# Naninator.net
KiCad netlist of a schematic drawn in EAGLE
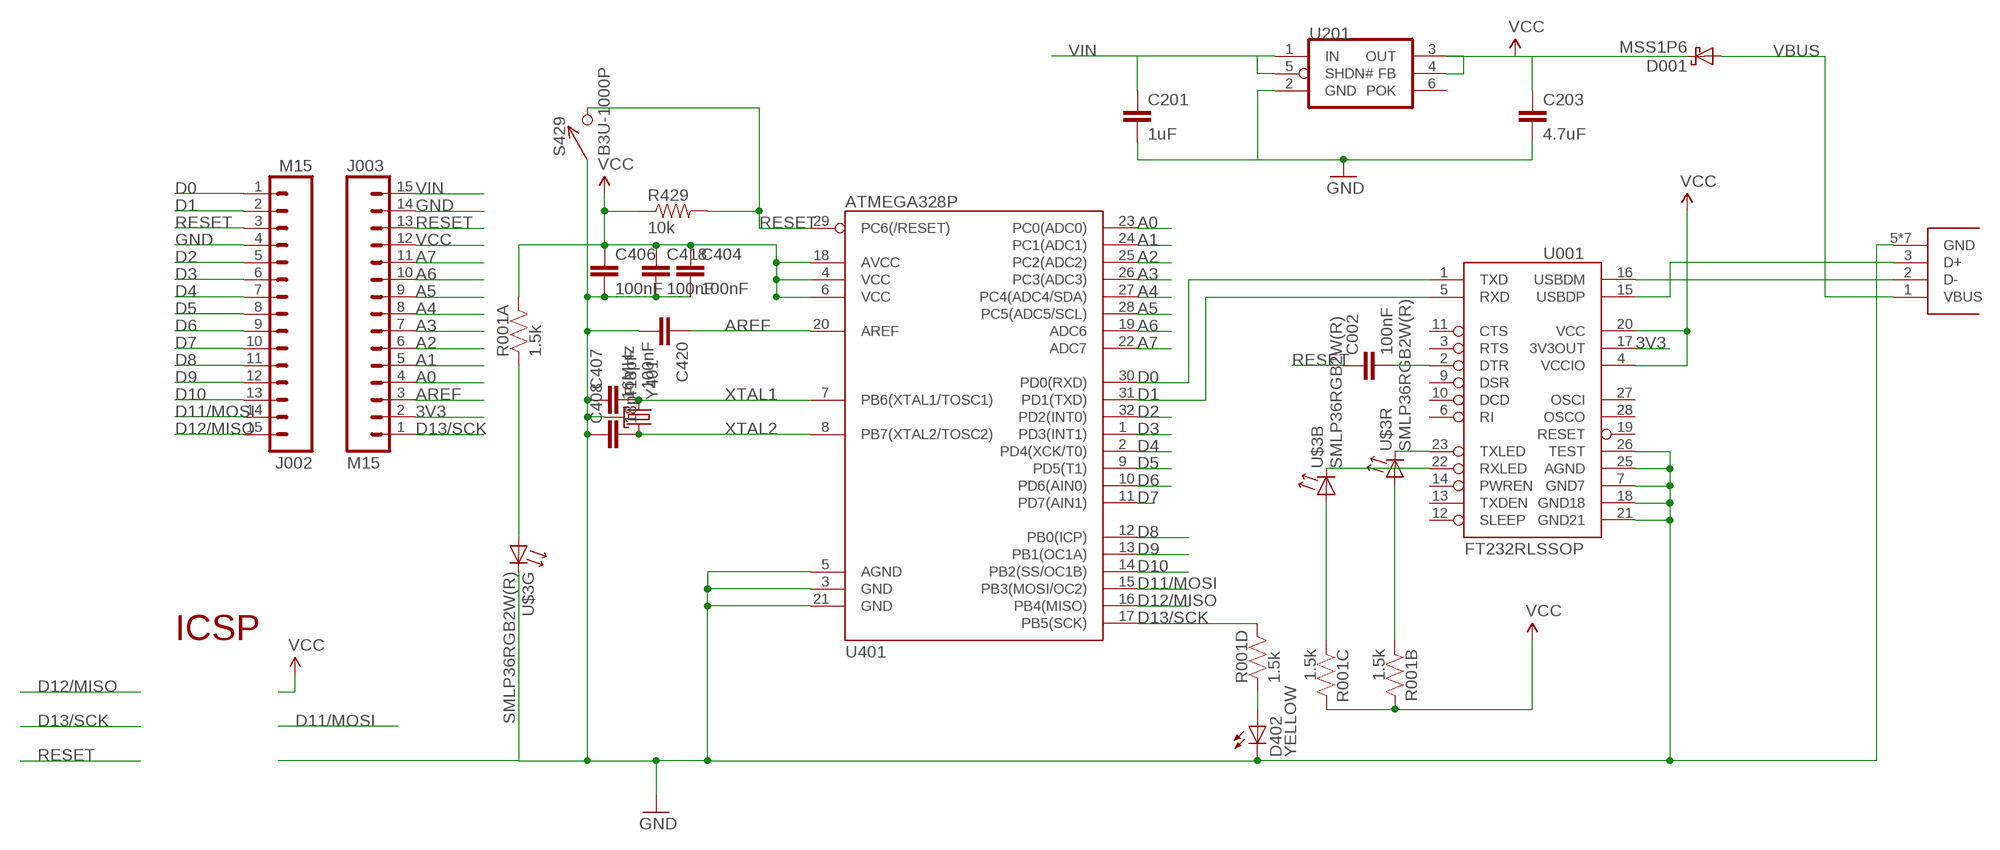
[diagram p0: schematic, sheet 1]

(export (version "E")
  (design (tool "Eeschema 10.0.6"))
  (components
    (comp (ref "C002")
      (value "100nF")
      (footprint "eagle-import:0402-CAP")
      (libsource (lib "eagle-import") (part "CAP0402-CAP"))
    )
    (comp (ref "C201")
      (value "1uF")
      (footprint "eagle-import:0402-CAP")
      (libsource (lib "eagle-import") (part "CAP0402-CAP"))
    )
    (comp (ref "C203")
      (value "4.7uF")
      (footprint "eagle-import:0402-CAP")
      (libsource (lib "eagle-import") (part "CAP0402-CAP"))
    )
    (comp (ref "C404")
      (value "100nF")
      (footprint "eagle-import:0402-CAP")
      (libsource (lib "eagle-import") (part "CAP0402-CAP"))
    )
    (comp (ref "C406")
      (value "100nF")
      (footprint "eagle-import:0402-CAP")
      (libsource (lib "eagle-import") (part "CAP0402-CAP"))
    )
    (comp (ref "C407")
      (value "18pF")
      (footprint "eagle-import:0402-CAP")
      (libsource (lib "eagle-import") (part "CAP0402-CAP"))
    )
    (comp (ref "C408")
      (value "18pF")
      (footprint "eagle-import:0402-CAP")
      (libsource (lib "eagle-import") (part "CAP0402-CAP"))
    )
    (comp (ref "C418")
      (value "100nF")
      (footprint "eagle-import:0402-CAP")
      (libsource (lib "eagle-import") (part "CAP0402-CAP"))
    )
    (comp (ref "C420")
      (value "100nF")
      (footprint "eagle-import:0402-CAP")
      (libsource (lib "eagle-import") (part "CAP0402-CAP"))
    )
    (comp (ref "D001")
      (value "MSS1P6")
      (footprint "eagle-import:MICROSMP")
      (libsource (lib "eagle-import") (part "MSS1P6"))
    )
    (comp (ref "D402")
      (value "YELLOW")
      (footprint "eagle-import:LED-0603")
      (libsource (lib "eagle-import") (part "LED0603"))
    )
    (comp (ref "J001")
      (value "USB_MICROB_JSTGCT")
      (footprint "eagle-import:USB_MICROB_3075")
      (libsource (lib "eagle-import") (part "USB_MICROB_JSTGCT"))
    )
    (comp (ref "J002")
      (value "M15")
      (footprint "eagle-import:1X15")
      (libsource (lib "eagle-import") (part "M15"))
    )
    (comp (ref "J003")
      (value "M15")
      (footprint "eagle-import:1X15")
      (libsource (lib "eagle-import") (part "M15"))
    )
    (comp (ref "R001")
      (value "1.5k")
      (footprint "eagle-import:CRA04")
      (fields (field (name "DIGIKEY") "CRA4S81.5KCT-ND"))
      (libsource (lib "eagle-import") (part "RP404"))
    )
    (comp (ref "R429")
      (value "10k")
      (footprint "eagle-import:0402-RES")
      (libsource (lib "eagle-import") (part "RESISTOR0402-RES"))
    )
    (comp (ref "S429")
      (value "B3U-1000P")
      (footprint "eagle-import:B3U-1000P")
      (libsource (lib "eagle-import") (part "B3U-1000P"))
    )
    (comp (ref "U$3")
      (value "SMLP36RGB2W(R)")
      (footprint "eagle-import:SMLP36")
      (libsource (lib "eagle-import") (part "SMLP36RGB2W(R)"))
    )
    (comp (ref "U001")
      (value "FT232RLSSOP")
      (footprint "eagle-import:SSOP28DB")
      (libsource (lib "eagle-import") (part "FT232RLSSOP"))
    )
    (comp (ref "U201")
      (value "MAX8881")
      (footprint "eagle-import:SOT-23-6")
      (libsource (lib "eagle-import") (part "MAX8881"))
    )
    (comp (ref "U401")
      (value "ATMEGA328P")
      (footprint "eagle-import:TQFP32-08")
      (libsource (lib "eagle-import") (part "ATMEGA168"))
    )
    (comp (ref "Y401")
      (value "16MHz")
      (footprint "eagle-import:CRYSTAL_SMD_2MM_1_6MM")
      (libsource (lib "eagle-import") (part "CX25208Y"))
    )
  )
  (nets
    (net (code "1") (name "/3V3") (class "Default")
      (node (ref "J003") (pin "2") (pinfunction "2_2") (pintype "passive"))
      (node (ref "U001") (pin "17") (pinfunction "3V3OUT_17") (pintype "output"))
    )
    (net (code "2") (name "/A0") (class "Default")
      (node (ref "J003") (pin "4") (pinfunction "4_4") (pintype "passive"))
      (node (ref "U401") (pin "23") (pinfunction "PC0(ADC0)_23") (pintype "bidirectional"))
    )
    (net (code "3") (name "/A1") (class "Default")
      (node (ref "J003") (pin "5") (pinfunction "5_5") (pintype "passive"))
      (node (ref "U401") (pin "24") (pinfunction "PC1(ADC1)_24") (pintype "bidirectional"))
    )
    (net (code "4") (name "/A2") (class "Default")
      (node (ref "J003") (pin "6") (pinfunction "6_6") (pintype "passive"))
      (node (ref "U401") (pin "25") (pinfunction "PC2(ADC2)_25") (pintype "bidirectional"))
    )
    (net (code "5") (name "/A3") (class "Default")
      (node (ref "J003") (pin "7") (pinfunction "7_7") (pintype "passive"))
      (node (ref "U401") (pin "26") (pinfunction "PC3(ADC3)_26") (pintype "bidirectional"))
    )
    (net (code "6") (name "/A4") (class "Default")
      (node (ref "J003") (pin "8") (pinfunction "8_8") (pintype "passive"))
      (node (ref "U401") (pin "27") (pinfunction "PC4(ADC4/SDA)_27") (pintype "bidirectional"))
    )
    (net (code "7") (name "/A5") (class "Default")
      (node (ref "J003") (pin "9") (pinfunction "9_9") (pintype "passive"))
      (node (ref "U401") (pin "28") (pinfunction "PC5(ADC5/SCL)_28") (pintype "bidirectional"))
    )
    (net (code "8") (name "/A6") (class "Default")
      (node (ref "J003") (pin "10") (pinfunction "10_10") (pintype "passive"))
      (node (ref "U401") (pin "19") (pinfunction "ADC6_19") (pintype "bidirectional"))
    )
    (net (code "9") (name "/A7") (class "Default")
      (node (ref "J003") (pin "11") (pinfunction "11_11") (pintype "passive"))
      (node (ref "U401") (pin "22") (pinfunction "ADC7_22") (pintype "bidirectional"))
    )
    (net (code "10") (name "/AREF") (class "Default")
      (node (ref "C420") (pin "1") (pinfunction "1_1") (pintype "passive"))
      (node (ref "J003") (pin "3") (pinfunction "3_3") (pintype "passive"))
      (node (ref "U401") (pin "20") (pinfunction "AREF_20") (pintype "bidirectional"))
    )
    (net (code "11") (name "/D0") (class "Default")
      (node (ref "J002") (pin "1") (pinfunction "1_1") (pintype "passive"))
      (node (ref "U001") (pin "1") (pinfunction "TXD_1") (pintype "output"))
      (node (ref "U401") (pin "30") (pinfunction "PD0(RXD)_30") (pintype "bidirectional"))
    )
    (net (code "12") (name "/D1") (class "Default")
      (node (ref "J002") (pin "2") (pinfunction "2_2") (pintype "passive"))
      (node (ref "U001") (pin "5") (pinfunction "RXD_5") (pintype "input"))
      (node (ref "U401") (pin "31") (pinfunction "PD1(TXD)_31") (pintype "bidirectional"))
    )
    (net (code "13") (name "/D2") (class "Default")
      (node (ref "J002") (pin "5") (pinfunction "5_5") (pintype "passive"))
      (node (ref "U401") (pin "32") (pinfunction "PD2(INT0)_32") (pintype "bidirectional"))
    )
    (net (code "14") (name "/D3") (class "Default")
      (node (ref "J002") (pin "6") (pinfunction "6_6") (pintype "passive"))
      (node (ref "U401") (pin "1") (pinfunction "PD3(INT1)_1") (pintype "bidirectional"))
    )
    (net (code "15") (name "/D4") (class "Default")
      (node (ref "J002") (pin "7") (pinfunction "7_7") (pintype "passive"))
      (node (ref "U401") (pin "2") (pinfunction "PD4(XCK/T0)_2") (pintype "bidirectional"))
    )
    (net (code "16") (name "/D5") (class "Default")
      (node (ref "J002") (pin "8") (pinfunction "8_8") (pintype "passive"))
      (node (ref "U401") (pin "9") (pinfunction "PD5(T1)_9") (pintype "bidirectional"))
    )
    (net (code "17") (name "/D6") (class "Default")
      (node (ref "J002") (pin "9") (pinfunction "9_9") (pintype "passive"))
      (node (ref "U401") (pin "10") (pinfunction "PD6(AIN0)_10") (pintype "bidirectional"))
    )
    (net (code "18") (name "/D7") (class "Default")
      (node (ref "J002") (pin "10") (pinfunction "10_10") (pintype "passive"))
      (node (ref "U401") (pin "11") (pinfunction "PD7(AIN1)_11") (pintype "bidirectional"))
    )
    (net (code "19") (name "/D8") (class "Default")
      (node (ref "J002") (pin "11") (pinfunction "11_11") (pintype "passive"))
      (node (ref "U401") (pin "12") (pinfunction "PB0(ICP)_12") (pintype "bidirectional"))
    )
    (net (code "20") (name "/D9") (class "Default")
      (node (ref "J002") (pin "12") (pinfunction "12_12") (pintype "passive"))
      (node (ref "U401") (pin "13") (pinfunction "PB1(OC1A)_13") (pintype "bidirectional"))
    )
    (net (code "21") (name "/D10") (class "Default")
      (node (ref "J002") (pin "13") (pinfunction "13_13") (pintype "passive"))
      (node (ref "U401") (pin "14") (pinfunction "PB2(SS/OC1B)_14") (pintype "bidirectional"))
    )
    (net (code "22") (name "/D11{slash}MOSI") (class "Default")
      (node (ref "J002") (pin "14") (pinfunction "14_14") (pintype "passive"))
      (node (ref "U401") (pin "15") (pinfunction "PB3(MOSI/OC2)_15") (pintype "bidirectional"))
    )
    (net (code "23") (name "/D12{slash}MISO") (class "Default")
      (node (ref "J002") (pin "15") (pinfunction "15_15") (pintype "passive"))
      (node (ref "U401") (pin "16") (pinfunction "PB4(MISO)_16") (pintype "bidirectional"))
    )
    (net (code "24") (name "/D13{slash}SCK") (class "Default")
      (node (ref "J003") (pin "1") (pinfunction "1_1") (pintype "passive"))
      (node (ref "R001") (pin "5") (pinfunction "2_5") (pintype "passive"))
      (node (ref "U401") (pin "17") (pinfunction "PB5(SCK)_17") (pintype "bidirectional"))
    )
    (net (code "25") (name "/RESET") (class "Default")
      (node (ref "C002") (pin "1") (pinfunction "1_1") (pintype "passive"))
      (node (ref "J002") (pin "3") (pinfunction "3_3") (pintype "passive"))
      (node (ref "J003") (pin "13") (pinfunction "13_13") (pintype "passive"))
      (node (ref "R429") (pin "2") (pinfunction "2_2") (pintype "passive"))
      (node (ref "S429") (pin "P$2") (pinfunction "2_P$2") (pintype "bidirectional"))
      (node (ref "U401") (pin "29") (pinfunction "PC6(/RESET)_29") (pintype "bidirectional"))
    )
    (net (code "26") (name "/VBUS") (class "Default")
      (node (ref "D001") (pin "A") (pinfunction "A_A") (pintype "passive"))
      (node (ref "J001") (pin "1") (pinfunction "VBUS_1") (pintype "bidirectional"))
    )
    (net (code "27") (name "/VIN") (class "Default")
      (node (ref "C201") (pin "1") (pinfunction "1_1") (pintype "passive"))
      (node (ref "J003") (pin "15") (pinfunction "15_15") (pintype "passive"))
      (node (ref "U201") (pin "1") (pinfunction "IN_1") (pintype "bidirectional"))
      (node (ref "U201") (pin "5") (pinfunction "SHDN#_5") (pintype "bidirectional"))
    )
    (net (code "28") (name "/XTAL1") (class "Default")
      (node (ref "C407") (pin "2") (pinfunction "2_2") (pintype "passive"))
      (node (ref "U401") (pin "7") (pinfunction "PB6(XTAL1/TOSC1)_7") (pintype "bidirectional"))
      (node (ref "Y401") (pin "3") (pinfunction "2_3") (pintype "passive"))
    )
    (net (code "29") (name "/XTAL2") (class "Default")
      (node (ref "C408") (pin "2") (pinfunction "2_2") (pintype "passive"))
      (node (ref "U401") (pin "8") (pinfunction "PB7(XTAL2/TOSC2)_8") (pintype "bidirectional"))
      (node (ref "Y401") (pin "1") (pinfunction "1_1") (pintype "passive"))
    )
    (net (code "30") (name "GND") (class "Default")
      (node (ref "C201") (pin "2") (pinfunction "2_2") (pintype "passive"))
      (node (ref "C203") (pin "2") (pinfunction "2_2") (pintype "passive"))
      (node (ref "C404") (pin "2") (pinfunction "2_2") (pintype "passive"))
      (node (ref "C406") (pin "2") (pinfunction "2_2") (pintype "passive"))
      (node (ref "C407") (pin "1") (pinfunction "1_1") (pintype "passive"))
      (node (ref "C408") (pin "1") (pinfunction "1_1") (pintype "passive"))
      (node (ref "C418") (pin "2") (pinfunction "2_2") (pintype "passive"))
      (node (ref "C420") (pin "2") (pinfunction "2_2") (pintype "passive"))
      (node (ref "D402") (pin "C") (pinfunction "C_C") (pintype "passive"))
      (node (ref "J001") (pin "5") (pinfunction "GND_5") (pintype "bidirectional"))
      (node (ref "J001") (pin "P$1") (pinfunction "GND_P$1") (pintype "bidirectional"))
      (node (ref "J001") (pin "P$10") (pinfunction "GND_P$10") (pintype "bidirectional"))
      (node (ref "J001") (pin "P$2") (pinfunction "GND_P$2") (pintype "bidirectional"))
      (node (ref "J001") (pin "P$3") (pinfunction "GND_P$3") (pintype "bidirectional"))
      (node (ref "J001") (pin "P$4") (pinfunction "GND_P$4") (pintype "bidirectional"))
      (node (ref "J001") (pin "P$8") (pinfunction "GND_P$8") (pintype "bidirectional"))
      (node (ref "J002") (pin "4") (pinfunction "4_4") (pintype "passive"))
      (node (ref "J003") (pin "14") (pinfunction "14_14") (pintype "passive"))
      (node (ref "S429") (pin "P$1") (pinfunction "1_P$1") (pintype "bidirectional"))
      (node (ref "U$3") (pin "5") (pinfunction "C_5") (pintype "passive"))
      (node (ref "U001") (pin "18") (pinfunction "GND18_18") (pintype "power_in"))
      (node (ref "U001") (pin "21") (pinfunction "GND21_21") (pintype "power_in"))
      (node (ref "U001") (pin "25") (pinfunction "AGND_25") (pintype "power_in"))
      (node (ref "U001") (pin "26") (pinfunction "TEST_26") (pintype "input"))
      (node (ref "U001") (pin "7") (pinfunction "GND7_7") (pintype "power_in"))
      (node (ref "U201") (pin "2") (pinfunction "GND_2") (pintype "bidirectional"))
      (node (ref "U401") (pin "21") (pinfunction "GND_21") (pintype "bidirectional"))
      (node (ref "U401") (pin "3") (pinfunction "GND_3") (pintype "bidirectional"))
      (node (ref "U401") (pin "5") (pinfunction "AGND_5") (pintype "bidirectional"))
      (node (ref "Y401") (pin "2") (pinfunction "GND_2") (pintype "passive"))
      (node (ref "Y401") (pin "4") (pinfunction "GND_4") (pintype "passive"))
    )
    (net (code "31") (name "Net-(J001-D+)") (class "Default")
      (node (ref "J001") (pin "3") (pinfunction "D+_3") (pintype "bidirectional"))
      (node (ref "U001") (pin "15") (pinfunction "USBDP_15") (pintype "bidirectional"))
    )
    (net (code "32") (name "Net-(J001-D-)") (class "Default")
      (node (ref "J001") (pin "2") (pinfunction "D-_2") (pintype "bidirectional"))
      (node (ref "U001") (pin "16") (pinfunction "USBDM_16") (pintype "bidirectional"))
    )
    (net (code "33") (name "Net-(R001B-1)") (class "Default")
      (node (ref "R001") (pin "2") (pinfunction "1_2") (pintype "passive"))
      (node (ref "U$3") (pin "4") (pinfunction "A_4") (pintype "passive"))
    )
    (net (code "34") (name "Net-(R001C-1)") (class "Default")
      (node (ref "R001") (pin "3") (pinfunction "1_3") (pintype "passive"))
      (node (ref "U$3") (pin "2") (pinfunction "A_2") (pintype "passive"))
    )
    (net (code "35") (name "Net-(R001D-1)") (class "Default")
      (node (ref "D402") (pin "A") (pinfunction "A_A") (pintype "passive"))
      (node (ref "R001") (pin "4") (pinfunction "1_4") (pintype "passive"))
    )
    (net (code "36") (name "Net-(U$3A-C)") (class "Default")
      (node (ref "U$3") (pin "1") (pinfunction "C_1") (pintype "passive"))
      (node (ref "U001") (pin "22") (pinfunction "RXLED_22") (pintype "input"))
    )
    (net (code "37") (name "Net-(U$3B-A)") (class "Default")
      (node (ref "R001") (pin "1") (pinfunction "1_1") (pintype "passive"))
      (node (ref "U$3") (pin "6") (pinfunction "A_6") (pintype "passive"))
    )
    (net (code "38") (name "Net-(U$3C-C)") (class "Default")
      (node (ref "U$3") (pin "3") (pinfunction "C_3") (pintype "passive"))
      (node (ref "U001") (pin "23") (pinfunction "TXLED_23") (pintype "input"))
    )
    (net (code "39") (name "Net-(U001-DTR)") (class "Default")
      (node (ref "C002") (pin "2") (pinfunction "2_2") (pintype "passive"))
      (node (ref "U001") (pin "2") (pinfunction "DTR_2") (pintype "output"))
    )
    (net (code "40") (name "VCC") (class "Default")
      (node (ref "C203") (pin "1") (pinfunction "1_1") (pintype "passive"))
      (node (ref "C404") (pin "1") (pinfunction "1_1") (pintype "passive"))
      (node (ref "C406") (pin "1") (pinfunction "1_1") (pintype "passive"))
      (node (ref "C418") (pin "1") (pinfunction "1_1") (pintype "passive"))
      (node (ref "D001") (pin "K") (pinfunction "K_K") (pintype "passive"))
      (node (ref "J003") (pin "12") (pinfunction "12_12") (pintype "passive"))
      (node (ref "R001") (pin "6") (pinfunction "2_6") (pintype "passive"))
      (node (ref "R001") (pin "7") (pinfunction "2_7") (pintype "passive"))
      (node (ref "R001") (pin "8") (pinfunction "2_8") (pintype "passive"))
      (node (ref "R429") (pin "1") (pinfunction "1_1") (pintype "passive"))
      (node (ref "U001") (pin "20") (pinfunction "VCC_20") (pintype "power_in"))
      (node (ref "U001") (pin "4") (pinfunction "VCCIO_4") (pintype "power_in"))
      (node (ref "U201") (pin "3") (pinfunction "OUT_3") (pintype "bidirectional"))
      (node (ref "U201") (pin "4") (pinfunction "FB_4") (pintype "bidirectional"))
      (node (ref "U401") (pin "18") (pinfunction "AVCC_18") (pintype "bidirectional"))
      (node (ref "U401") (pin "4") (pinfunction "VCC_4") (pintype "bidirectional"))
      (node (ref "U401") (pin "6") (pinfunction "VCC_6") (pintype "bidirectional"))
    )
    (net (code "41") (name "unconnected-(U001-CTS-Pad11)") (class "Default")
      (node (ref "U001") (pin "11") (pinfunction "CTS_11") (pintype "input"))
    )
    (net (code "42") (name "unconnected-(U001-DCD-Pad10)") (class "Default")
      (node (ref "U001") (pin "10") (pinfunction "DCD_10") (pintype "input"))
    )
    (net (code "43") (name "unconnected-(U001-DSR-Pad9)") (class "Default")
      (node (ref "U001") (pin "9") (pinfunction "DSR_9") (pintype "input"))
    )
    (net (code "44") (name "unconnected-(U001-OSCI-Pad27)") (class "Default")
      (node (ref "U001") (pin "27") (pinfunction "OSCI_27") (pintype "input"))
    )
    (net (code "45") (name "unconnected-(U001-OSCO-Pad28)") (class "Default")
      (node (ref "U001") (pin "28") (pinfunction "OSCO_28") (pintype "output"))
    )
    (net (code "46") (name "unconnected-(U001-PWREN-Pad14)") (class "Default")
      (node (ref "U001") (pin "14") (pinfunction "PWREN_14") (pintype "input"))
    )
    (net (code "47") (name "unconnected-(U001-RESET-Pad19)") (class "Default")
      (node (ref "U001") (pin "19") (pinfunction "RESET_19") (pintype "input"))
    )
    (net (code "48") (name "unconnected-(U001-RI-Pad6)") (class "Default")
      (node (ref "U001") (pin "6") (pinfunction "RI_6") (pintype "input"))
    )
    (net (code "49") (name "unconnected-(U001-RTS-Pad3)") (class "Default")
      (node (ref "U001") (pin "3") (pinfunction "RTS_3") (pintype "output"))
    )
    (net (code "50") (name "unconnected-(U001-SLEEP-Pad12)") (class "Default")
      (node (ref "U001") (pin "12") (pinfunction "SLEEP_12") (pintype "input"))
    )
    (net (code "51") (name "unconnected-(U001-TXDEN-Pad13)") (class "Default")
      (node (ref "U001") (pin "13") (pinfunction "TXDEN_13") (pintype "input"))
    )
    (net (code "52") (name "unconnected-(U201-POK-Pad6)") (class "Default")
      (node (ref "U201") (pin "6") (pinfunction "POK_6") (pintype "bidirectional"))
    )
  )
)
